# CH32F_V208W-R0.net
KiCad netlist of a schematic drawn in Altium Designer
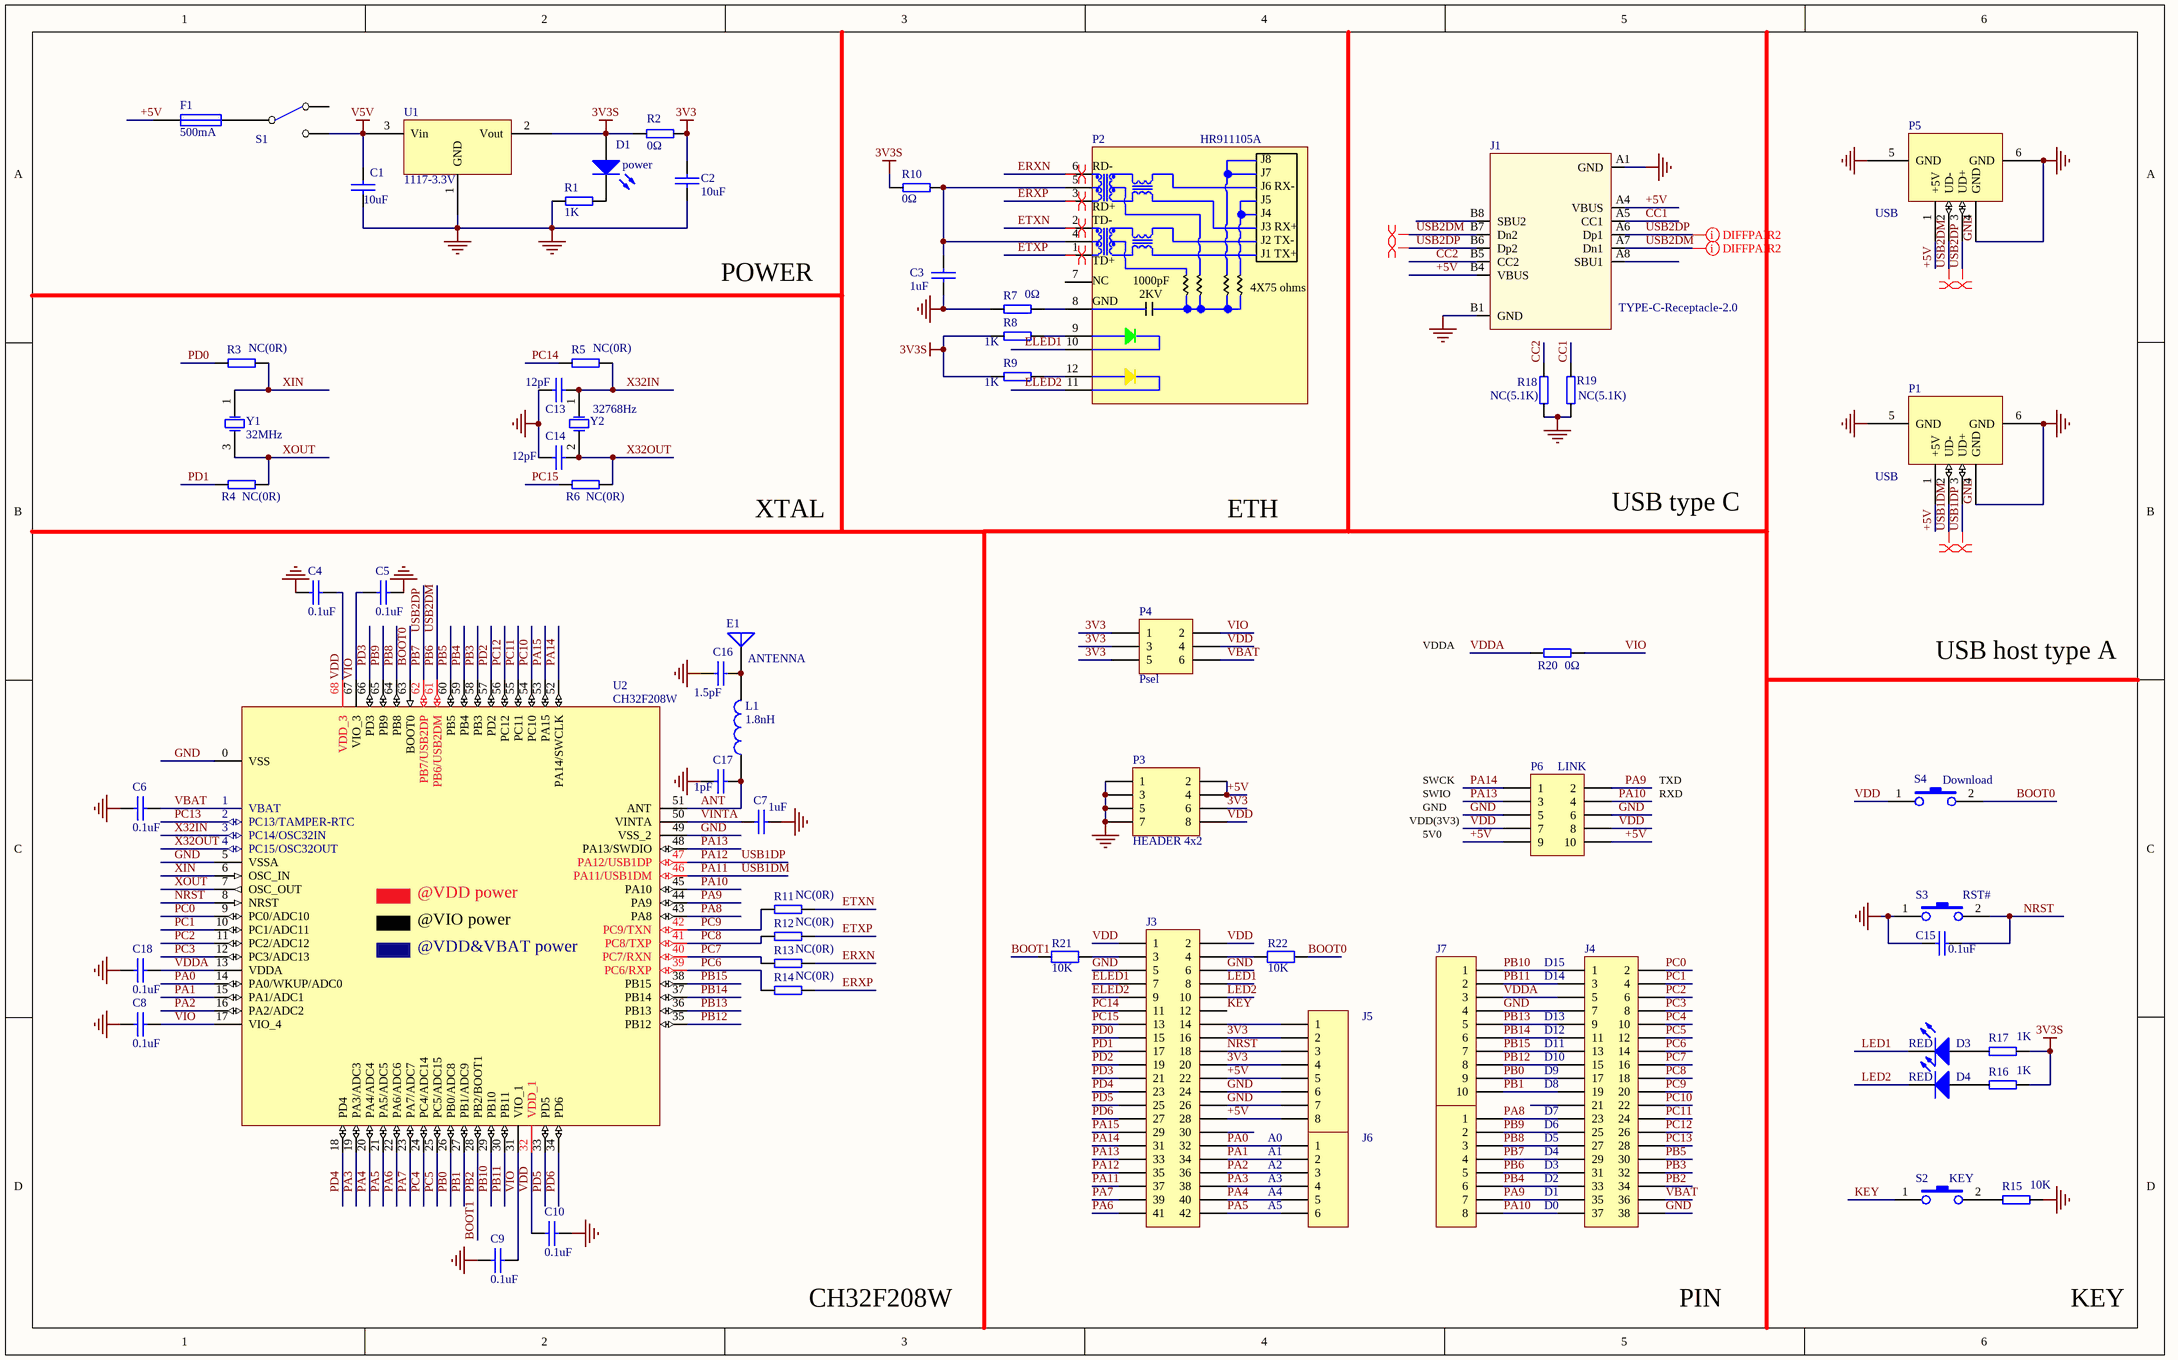
[diagram p0: CH32F&V208W-R0.SchDoc]

(export (version "E")
  (design (tool "Eeschema 10.0.6"))
  (components
    (comp (ref "C1")
      (value "10uF")
      (footprint "3216_C")
      (description "Capacitor")
      (libsource (lib "") (part "CAP_1"))
    )
    (comp (ref "C2")
      (value "10uF")
      (footprint "0603_C")
      (description "Capacitor")
      (libsource (lib "") (part "CAP_1"))
    )
    (comp (ref "C3")
      (value "1uF")
      (footprint "0603_C")
      (description "Capacitor")
      (libsource (lib "") (part "CAP_1"))
    )
    (comp (ref "C4")
      (value "0.1uF")
      (footprint "0603_C")
      (description "Capacitor")
      (libsource (lib "*") (part "CAP"))
    )
    (comp (ref "C5")
      (value "0.1uF")
      (footprint "0603_C")
      (description "Capacitor")
      (libsource (lib "*") (part "CAP"))
    )
    (comp (ref "C6")
      (value "0.1uF")
      (footprint "0603_C")
      (description "Capacitor")
      (libsource (lib "*") (part "CAP"))
    )
    (comp (ref "C7")
      (value "1uF")
      (footprint "0603_C")
      (description "Capacitor")
      (libsource (lib "*") (part "CAP"))
    )
    (comp (ref "C8")
      (value "0.1uF")
      (footprint "0603_C")
      (description "Capacitor")
      (libsource (lib "*") (part "CAP"))
    )
    (comp (ref "C9")
      (value "0.1uF")
      (footprint "0603_C")
      (description "Capacitor")
      (libsource (lib "*") (part "CAP"))
    )
    (comp (ref "C10")
      (value "0.1uF")
      (footprint "0603_C")
      (description "Capacitor")
      (libsource (lib "*") (part "CAP"))
    )
    (comp (ref "C13")
      (value "12pF")
      (footprint "0603_C")
      (description "Capacitor")
      (libsource (lib "") (part "CAP_1"))
    )
    (comp (ref "C14")
      (value "12pF")
      (footprint "0603_C")
      (description "Capacitor")
      (libsource (lib "") (part "CAP_1"))
    )
    (comp (ref "C15")
      (value "0.1uF")
      (footprint "0603_C")
      (description "Capacitor")
      (libsource (lib "*") (part "CAP"))
    )
    (comp (ref "C16")
      (value "1.5pF")
      (footprint "0603_C")
      (description "Capacitor")
      (libsource (lib "*") (part "CAP"))
    )
    (comp (ref "C17")
      (value "1pF")
      (footprint "0603_C")
      (description "Capacitor")
      (libsource (lib "*") (part "CAP"))
    )
    (comp (ref "C18")
      (value "0.1uF")
      (footprint "0603_C")
      (description "Capacitor")
      (libsource (lib "*") (part "CAP"))
    )
    (comp (ref "D1")
      (value "power")
      (footprint "0603+")
      (description "Typical INFRARED GaAs LED")
      (fields (field (name "PUBLISHER") "Altium Limited"))
      (libsource (lib "*") (part "LED0"))
    )
    (comp (ref "D3")
      (value "RED")
      (footprint "0603+")
      (description "Typical INFRARED GaAs LED")
      (fields (field (name "PUBLISHER") "Altium Limited"))
      (libsource (lib "*") (part "LED0"))
    )
    (comp (ref "D4")
      (value "RED")
      (footprint "0603+")
      (description "Typical INFRARED GaAs LED")
      (fields (field (name "PUBLISHER") "Altium Limited"))
      (libsource (lib "*") (part "LED0"))
    )
    (comp (ref "E1")
      (value "ANTENNA")
      (footprint "MYPCB:ANT-F-1-2.4G-1.6")
      (description "Generic Antenna")
      (libsource (lib "*") (part "ANTENNA"))
    )
    (comp (ref "F1")
      (value "500mA")
      (footprint "0603")
      (description "Fuse")
      (libsource (lib "wch_sch_others") (part "FUSE1"))
    )
    (comp (ref "J1")
      (value "TYPE-C-Receptacle-2.0")
      (footprint "TYPE-C-Receptacle-2.0")
      (description "Type-C USB2.0 母座")
      (libsource (lib "Miscellaneous SCH Lib") (part "TYPE-C-Receptacle-2.0"))
    )
    (comp (ref "J3")
      (value "Header 21X2")
      (footprint "IDC42-2.54mm")
      (description "Header, 21-Pin, Dual row")
      (fields (field (name "PUBLISHER") "Altium Limited"))
      (libsource (lib "PCB_Project") (part "Header 21X2"))
    )
    (comp (ref "J4")
      (value "Header 19X2")
      (footprint "IDC38-2.54mm")
      (description "Header, 19-Pin, Dual row")
      (fields (field (name "PUBLISHER") "Altium Limited"))
      (libsource (lib "Miscellaneous Connectors") (part "Header 19X2"))
    )
    (comp (ref "J5")
      (value "Header 8")
      (footprint "SIP8-2.54mm")
      (description "Header, 8-Pin")
      (fields (field (name "PUBLISHER") "Altium Limited"))
      (libsource (lib "Miscellaneous Connectors") (part "Header 8"))
    )
    (comp (ref "J6")
      (value "Header 6")
      (footprint "SIP6-2.54MM")
      (description "Header, 6-Pin")
      (fields (field (name "PUBLISHER") "Altium Limited"))
      (libsource (lib "Miscellaneous Connectors") (part "Header 6"))
    )
    (comp (ref "J7")
      (value "Header 10")
      (footprint "SIP10-2.54mm")
      (description "Header, 10-Pin")
      (fields (field (name "PUBLISHER") "Altium Limited"))
      (libsource (lib "Miscellaneous Connectors") (part "Header 10"))
    )
    (comp (ref "J8")
      (value "Header 8")
      (footprint "SIP8-2.54mm")
      (description "Header, 8-Pin")
      (fields (field (name "PUBLISHER") "Altium Limited"))
      (libsource (lib "") (part "Header 8_1"))
    )
    (comp (ref "L1") (value "1.8nH") (footprint "0603") (libsource (lib "*") (part "INDUCTOR")))
    (comp (ref "P1")
      (value "USB")
      (footprint "USBAF")
      (description "USB Port")
      (libsource (lib "*") (part "USB"))
    )
    (comp (ref "P2") (value "HR911105A") (footprint "HR911105A") (libsource (lib "*") (part "HR911105A")))
    (comp (ref "P3")
      (value "HEADER 4x2")
      (footprint "MYPCB:IDC8-2.54mm")
      (description "Header, 4-Pin, Dual row")
      (libsource (lib "wch_sch_others") (part "HEADER 4x2"))
    )
    (comp (ref "P4")
      (value "Psel")
      (footprint "IDC6-2.54mm")
      (description "Header, 3-Pin, Dual row, Right Angle")
      (fields (field (name "PUBLISHER") "Altium Limited"))
      (libsource (lib "Miscellaneous Connectors") (part "Header 3X2H"))
    )
    (comp (ref "P5")
      (value "USB")
      (footprint "USBAF")
      (description "USB Port")
      (libsource (lib "*") (part "USB"))
    )
    (comp (ref "P6")
      (value "LINK")
      (footprint "IDC10-2.54mm")
      (description "Header, 5-Pin, Dual row, Right Angle")
      (fields (field (name "PUBLISHER") "Altium Limited"))
      (libsource (lib "Miscellaneous Connectors") (part "Header 5X2H"))
    )
    (comp (ref "R1") (value "1K") (footprint "0603") (libsource (lib "wch_sch_others") (part "RES")))
    (comp (ref "R2") (value "0Ω") (footprint "0603") (libsource (lib "wch_sch_others") (part "RES")))
    (comp (ref "R3") (value "NC(0R)") (footprint "0603") (libsource (lib "wch_sch_others") (part "RES")))
    (comp (ref "R4") (value "NC(0R)") (footprint "0603") (libsource (lib "wch_sch_others") (part "RES")))
    (comp (ref "R5") (value "NC(0R)") (footprint "0603") (libsource (lib "wch_sch_others") (part "RES")))
    (comp (ref "R6") (value "NC(0R)") (footprint "0603") (libsource (lib "wch_sch_others") (part "RES")))
    (comp (ref "R7") (value "0Ω") (footprint "0603") (libsource (lib "wch_sch_others") (part "RES")))
    (comp (ref "R8") (value "1K") (footprint "0603") (libsource (lib "wch_sch_others") (part "RES")))
    (comp (ref "R9") (value "1K") (footprint "0603") (libsource (lib "wch_sch_others") (part "RES")))
    (comp (ref "R10") (value "0Ω") (footprint "0603") (libsource (lib "wch_sch_others") (part "RES")))
    (comp (ref "R11") (value "NC(0R)") (footprint "0603") (libsource (lib "wch_sch_others") (part "RES")))
    (comp (ref "R12") (value "NC(0R)") (footprint "0603") (libsource (lib "wch_sch_others") (part "RES")))
    (comp (ref "R13") (value "NC(0R)") (footprint "0603") (libsource (lib "wch_sch_others") (part "RES")))
    (comp (ref "R14") (value "NC(0R)") (footprint "0603") (libsource (lib "wch_sch_others") (part "RES")))
    (comp (ref "R15") (value "10K") (footprint "0603") (libsource (lib "wch_sch_others") (part "RES")))
    (comp (ref "R16") (value "1K") (footprint "0603") (libsource (lib "wch_sch_others") (part "RES")))
    (comp (ref "R17") (value "1K") (footprint "0603") (libsource (lib "wch_sch_others") (part "RES")))
    (comp (ref "R18") (value "NC(5.1K)") (footprint "0603") (libsource (lib "wch_sch_others") (part "RES")))
    (comp (ref "R19") (value "NC(5.1K)") (footprint "0603") (libsource (lib "wch_sch_others") (part "RES")))
    (comp (ref "R20") (value "0Ω") (footprint "0603") (libsource (lib "*") (part "R")))
    (comp (ref "R21")
      (value "10K")
      (footprint "0603")
      (description "Resistor")
      (libsource (lib "Miscellaneous Devices") (part "Res2"))
    )
    (comp (ref "R22")
      (value "10K")
      (footprint "0603")
      (description "Resistor")
      (libsource (lib "Miscellaneous Devices") (part "Res2"))
    )
    (comp (ref "S1") (value "SW SPDT") (footprint "KEY_B") (libsource (lib "*") (part "SW SPDT")))
    (comp (ref "S2")
      (value "KEY")
      (footprint "SMD_6.1x3.65x2.5mm-KEY")
      (libsource (lib "wch_sch_others") (part "KEY1"))
    )
    (comp (ref "S3")
      (value "RST#")
      (footprint "SMD_6.1x3.65x2.5mm-KEY")
      (libsource (lib "wch_sch_others") (part "KEY1"))
    )
    (comp (ref "S4")
      (value "Download")
      (footprint "SMD_6.1x3.65x2.5mm-KEY")
      (libsource (lib "wch_sch_others") (part "KEY1"))
    )
    (comp (ref "U1")
      (value "1117-3.3V")
      (footprint "SOT-223")
      (libsource (lib "wch_sch_others") (part "1117-3.3V"))
    )
    (comp (ref "U2")
      (value "CH32F208W")
      (footprint "QFN68_8x8")
      (description "ARM M3 BLE5.3 MCU, 10M Ethernet, 2*USB, CAN")
      (libsource (lib "CHXXX") (part "CH32F208W"))
    )
    (comp (ref "Y1")
      (value "32MHz")
      (footprint "XT3225")
      (description "Crystal Oscillator")
      (fields (field (name "PUBLISHER") "Altium Limited"))
      (libsource (lib "") (part "XTAL_1"))
    )
    (comp (ref "Y2")
      (value "32768Hz")
      (footprint "FC-135")
      (description "Crystal Oscillator")
      (fields (field (name "PUBLISHER") "Altium Limited"))
      (libsource (lib "*") (part "XTAL"))
    )
  )
  (nets
    (net (code "1") (name "/+5V") (class "Default")
      (node (ref "F1") (pin "1") (pinfunction "1_1") (pintype "passive"))
      (node (ref "J1") (pin "A4") (pinfunction "VBUS_A4") (pintype "passive"))
      (node (ref "J1") (pin "B4") (pinfunction "VBUS_B4") (pintype "passive"))
      (node (ref "J3") (pin "22") (pinfunction "22_22") (pintype "passive"))
      (node (ref "J3") (pin "28") (pinfunction "28_28") (pintype "passive"))
      (node (ref "J5") (pin "5") (pinfunction "5_5") (pintype "passive"))
      (node (ref "J5") (pin "8") (pinfunction "8_8") (pintype "passive"))
      (node (ref "P1") (pin "1") (pinfunction "+5V_1") (pintype "power_in"))
      (node (ref "P3") (pin "2") (pinfunction "2_2") (pintype "passive"))
      (node (ref "P3") (pin "4") (pinfunction "4_4") (pintype "passive"))
      (node (ref "P5") (pin "1") (pinfunction "+5V_1") (pintype "power_in"))
      (node (ref "P6") (pin "10") (pinfunction "10_10") (pintype "passive"))
      (node (ref "P6") (pin "9") (pinfunction "9_9") (pintype "passive"))
    )
    (net (code "2") (name "/ANT") (class "Default")
      (node (ref "C17") (pin "2") (pinfunction "2_2") (pintype "passive"))
      (node (ref "L1") (pin "1") (pinfunction "1_1") (pintype "passive"))
      (node (ref "U2") (pin "51") (pinfunction "ANT_51") (pintype "power_in"))
    )
    (net (code "3") (name "/BOOT0") (class "Default")
      (node (ref "R22") (pin "2") (pinfunction "2_2") (pintype "passive"))
      (node (ref "S4") (pin "2") (pinfunction "2_2") (pintype "passive"))
      (node (ref "U2") (pin "63") (pinfunction "BOOT0_63") (pintype "input"))
    )
    (net (code "4") (name "/BOOT1") (class "Default")
      (node (ref "J4") (pin "34") (pinfunction "34_34") (pintype "passive"))
      (node (ref "R21") (pin "1") (pinfunction "1_1") (pintype "passive"))
      (node (ref "U2") (pin "28") (pinfunction "PB2/BOOT1_28") (pintype "bidirectional"))
    )
    (net (code "5") (name "/CC1") (class "Default")
      (node (ref "J1") (pin "A5") (pinfunction "CC1_A5") (pintype "passive"))
      (node (ref "R19") (pin "1") (pintype "passive"))
    )
    (net (code "6") (name "/CC2") (class "Default")
      (node (ref "J1") (pin "B5") (pinfunction "CC2_B5") (pintype "passive"))
      (node (ref "R18") (pin "1") (pintype "passive"))
    )
    (net (code "7") (name "/ELED1") (class "Default")
      (node (ref "J3") (pin "7") (pinfunction "7_7") (pintype "passive"))
      (node (ref "P2") (pin "10") (pintype "passive"))
    )
    (net (code "8") (name "/ELED2") (class "Default")
      (node (ref "J3") (pin "9") (pinfunction "9_9") (pintype "passive"))
      (node (ref "P2") (pin "11") (pintype "passive"))
    )
    (net (code "9") (name "/ERXN") (class "Default")
      (node (ref "P2") (pin "6") (pintype "passive"))
      (node (ref "R13") (pin "2") (pintype "passive"))
    )
    (net (code "10") (name "/ERXP") (class "Default")
      (node (ref "P2") (pin "3") (pintype "passive"))
      (node (ref "R14") (pin "2") (pintype "passive"))
    )
    (net (code "11") (name "/ETXN") (class "Default")
      (node (ref "P2") (pin "2") (pintype "passive"))
      (node (ref "R11") (pin "2") (pintype "passive"))
    )
    (net (code "12") (name "/ETXP") (class "Default")
      (node (ref "P2") (pin "1") (pintype "passive"))
      (node (ref "R12") (pin "2") (pintype "passive"))
    )
    (net (code "13") (name "/KEY") (class "Default")
      (node (ref "J3") (pin "12") (pinfunction "12_12") (pintype "passive"))
      (node (ref "S2") (pin "1") (pinfunction "1_1") (pintype "passive"))
    )
    (net (code "14") (name "/LED1") (class "Default")
      (node (ref "D3") (pin "2") (pinfunction "K_2") (pintype "passive"))
      (node (ref "J3") (pin "8") (pinfunction "8_8") (pintype "passive"))
    )
    (net (code "15") (name "/LED2") (class "Default")
      (node (ref "D4") (pin "2") (pinfunction "K_2") (pintype "passive"))
      (node (ref "J3") (pin "10") (pinfunction "10_10") (pintype "passive"))
    )
    (net (code "16") (name "/NRST") (class "Default")
      (node (ref "C15") (pin "2") (pinfunction "2_2") (pintype "passive"))
      (node (ref "J3") (pin "18") (pinfunction "18_18") (pintype "passive"))
      (node (ref "J5") (pin "3") (pinfunction "3_3") (pintype "passive"))
      (node (ref "S3") (pin "2") (pinfunction "2_2") (pintype "passive"))
      (node (ref "U2") (pin "8") (pinfunction "NRST_8") (pintype "input"))
    )
    (net (code "17") (name "/PA0") (class "Default")
      (node (ref "J3") (pin "32") (pinfunction "32_32") (pintype "passive"))
      (node (ref "J6") (pin "1") (pinfunction "1_1") (pintype "passive"))
      (node (ref "U2") (pin "14") (pinfunction "PA0/WKUP/ADC0_14") (pintype "bidirectional"))
    )
    (net (code "18") (name "/PA1") (class "Default")
      (node (ref "J3") (pin "34") (pinfunction "34_34") (pintype "passive"))
      (node (ref "J6") (pin "2") (pinfunction "2_2") (pintype "passive"))
      (node (ref "U2") (pin "15") (pinfunction "PA1/ADC1_15") (pintype "bidirectional"))
    )
    (net (code "19") (name "/PA2") (class "Default")
      (node (ref "J3") (pin "36") (pinfunction "36_36") (pintype "passive"))
      (node (ref "J6") (pin "3") (pinfunction "3_3") (pintype "passive"))
      (node (ref "U2") (pin "16") (pinfunction "PA2/ADC2_16") (pintype "bidirectional"))
    )
    (net (code "20") (name "/PA3") (class "Default")
      (node (ref "J3") (pin "38") (pinfunction "38_38") (pintype "passive"))
      (node (ref "J6") (pin "4") (pinfunction "4_4") (pintype "passive"))
      (node (ref "U2") (pin "19") (pinfunction "PA3/ADC3_19") (pintype "bidirectional"))
    )
    (net (code "21") (name "/PA4") (class "Default")
      (node (ref "J3") (pin "40") (pinfunction "40_40") (pintype "passive"))
      (node (ref "J6") (pin "5") (pinfunction "5_5") (pintype "passive"))
      (node (ref "U2") (pin "20") (pinfunction "PA4/ADC4_20") (pintype "bidirectional"))
    )
    (net (code "22") (name "/PA5") (class "Default")
      (node (ref "J3") (pin "42") (pinfunction "42_42") (pintype "passive"))
      (node (ref "J6") (pin "6") (pinfunction "6_6") (pintype "passive"))
      (node (ref "U2") (pin "21") (pinfunction "PA5/ADC5_21") (pintype "bidirectional"))
    )
    (net (code "23") (name "/PA6") (class "Default")
      (node (ref "J3") (pin "41") (pinfunction "41_41") (pintype "passive"))
      (node (ref "U2") (pin "22") (pinfunction "PA6/ADC6_22") (pintype "bidirectional"))
    )
    (net (code "24") (name "/PA7") (class "Default")
      (node (ref "J3") (pin "39") (pinfunction "39_39") (pintype "passive"))
      (node (ref "U2") (pin "23") (pinfunction "PA7/ADC7_23") (pintype "bidirectional"))
    )
    (net (code "25") (name "/PA8") (class "Default")
      (node (ref "J4") (pin "23") (pinfunction "23_23") (pintype "passive"))
      (node (ref "J8") (pin "1") (pinfunction "1_1") (pintype "passive"))
      (node (ref "U2") (pin "43") (pinfunction "PA8_43") (pintype "bidirectional"))
    )
    (net (code "26") (name "/PA9") (class "Default")
      (node (ref "J4") (pin "35") (pinfunction "35_35") (pintype "passive"))
      (node (ref "J8") (pin "7") (pinfunction "7_7") (pintype "passive"))
      (node (ref "P6") (pin "2") (pinfunction "2_2") (pintype "passive"))
      (node (ref "U2") (pin "44") (pinfunction "PA9_44") (pintype "bidirectional"))
    )
    (net (code "27") (name "/PA10") (class "Default")
      (node (ref "J4") (pin "37") (pinfunction "37_37") (pintype "passive"))
      (node (ref "J8") (pin "8") (pinfunction "8_8") (pintype "passive"))
      (node (ref "P6") (pin "4") (pinfunction "4_4") (pintype "passive"))
      (node (ref "U2") (pin "45") (pinfunction "PA10_45") (pintype "bidirectional"))
    )
    (net (code "28") (name "/PA11") (class "Default")
      (node (ref "J3") (pin "37") (pinfunction "37_37") (pintype "passive"))
      (node (ref "P1") (pin "2") (pinfunction "UD-_2") (pintype "bidirectional"))
      (node (ref "U2") (pin "46") (pinfunction "PA11/USB1DM_46") (pintype "bidirectional"))
    )
    (net (code "29") (name "/PA12") (class "Default")
      (node (ref "J3") (pin "35") (pinfunction "35_35") (pintype "passive"))
      (node (ref "P1") (pin "3") (pinfunction "UD+_3") (pintype "bidirectional"))
      (node (ref "U2") (pin "47") (pinfunction "PA12/USB1DP_47") (pintype "bidirectional"))
    )
    (net (code "30") (name "/PA13") (class "Default")
      (node (ref "J3") (pin "33") (pinfunction "33_33") (pintype "passive"))
      (node (ref "P6") (pin "3") (pinfunction "3_3") (pintype "passive"))
      (node (ref "U2") (pin "48") (pinfunction "PA13/SWDIO_48") (pintype "bidirectional"))
    )
    (net (code "31") (name "/PA14") (class "Default")
      (node (ref "J3") (pin "31") (pinfunction "31_31") (pintype "passive"))
      (node (ref "P6") (pin "1") (pinfunction "1_1") (pintype "passive"))
      (node (ref "U2") (pin "52") (pinfunction "PA14/SWCLK_52") (pintype "bidirectional"))
    )
    (net (code "32") (name "/PA15") (class "Default")
      (node (ref "J3") (pin "29") (pinfunction "29_29") (pintype "passive"))
      (node (ref "U2") (pin "53") (pinfunction "PA15_53") (pintype "bidirectional"))
    )
    (net (code "33") (name "/PB0") (class "Default")
      (node (ref "J4") (pin "17") (pinfunction "17_17") (pintype "passive"))
      (node (ref "J7") (pin "9") (pinfunction "9_9") (pintype "passive"))
      (node (ref "U2") (pin "26") (pinfunction "PB0/ADC8_26") (pintype "bidirectional"))
    )
    (net (code "34") (name "/PB1") (class "Default")
      (node (ref "J4") (pin "19") (pinfunction "19_19") (pintype "passive"))
      (node (ref "J7") (pin "10") (pinfunction "10_10") (pintype "passive"))
      (node (ref "U2") (pin "27") (pinfunction "PB1/ADC9_27") (pintype "bidirectional"))
    )
    (net (code "35") (name "/PB3") (class "Default")
      (node (ref "J4") (pin "32") (pinfunction "32_32") (pintype "passive"))
      (node (ref "U2") (pin "58") (pinfunction "PB3_58") (pintype "bidirectional"))
    )
    (net (code "36") (name "/PB4") (class "Default")
      (node (ref "J4") (pin "33") (pinfunction "33_33") (pintype "passive"))
      (node (ref "J8") (pin "6") (pinfunction "6_6") (pintype "passive"))
      (node (ref "U2") (pin "59") (pinfunction "PB4_59") (pintype "bidirectional"))
    )
    (net (code "37") (name "/PB5") (class "Default")
      (node (ref "J4") (pin "30") (pinfunction "30_30") (pintype "passive"))
      (node (ref "U2") (pin "60") (pinfunction "PB5_60") (pintype "bidirectional"))
    )
    (net (code "38") (name "/PB6") (class "Default")
      (node (ref "J1") (pin "A7") (pinfunction "Dn1_A7") (pintype "passive"))
      (node (ref "J1") (pin "B7") (pinfunction "Dn2_B7") (pintype "passive"))
      (node (ref "J4") (pin "31") (pinfunction "31_31") (pintype "passive"))
      (node (ref "J8") (pin "5") (pinfunction "5_5") (pintype "passive"))
      (node (ref "P5") (pin "2") (pinfunction "UD-_2") (pintype "bidirectional"))
      (node (ref "U2") (pin "61") (pinfunction "PB6/USB2DM_61") (pintype "bidirectional"))
    )
    (net (code "39") (name "/PB7") (class "Default")
      (node (ref "J1") (pin "A6") (pinfunction "Dp1_A6") (pintype "passive"))
      (node (ref "J1") (pin "B6") (pinfunction "Dp2_B6") (pintype "passive"))
      (node (ref "J4") (pin "29") (pinfunction "29_29") (pintype "passive"))
      (node (ref "J8") (pin "4") (pinfunction "4_4") (pintype "passive"))
      (node (ref "P5") (pin "3") (pinfunction "UD+_3") (pintype "bidirectional"))
      (node (ref "U2") (pin "62") (pinfunction "PB7/USB2DP_62") (pintype "bidirectional"))
    )
    (net (code "40") (name "/PB8") (class "Default")
      (node (ref "J4") (pin "27") (pinfunction "27_27") (pintype "passive"))
      (node (ref "J8") (pin "3") (pinfunction "3_3") (pintype "passive"))
      (node (ref "U2") (pin "64") (pinfunction "PB8_64") (pintype "bidirectional"))
    )
    (net (code "41") (name "/PB9") (class "Default")
      (node (ref "J4") (pin "25") (pinfunction "25_25") (pintype "passive"))
      (node (ref "J8") (pin "2") (pinfunction "2_2") (pintype "passive"))
      (node (ref "U2") (pin "65") (pinfunction "PB9_65") (pintype "bidirectional"))
    )
    (net (code "42") (name "/PB10") (class "Default")
      (node (ref "J4") (pin "1") (pinfunction "1_1") (pintype "passive"))
      (node (ref "J7") (pin "1") (pinfunction "1_1") (pintype "passive"))
      (node (ref "U2") (pin "29") (pinfunction "PB10_29") (pintype "bidirectional"))
    )
    (net (code "43") (name "/PB11") (class "Default")
      (node (ref "J4") (pin "3") (pinfunction "3_3") (pintype "passive"))
      (node (ref "J7") (pin "2") (pinfunction "2_2") (pintype "passive"))
      (node (ref "U2") (pin "30") (pinfunction "PB11_30") (pintype "bidirectional"))
    )
    (net (code "44") (name "/PB12") (class "Default")
      (node (ref "J4") (pin "15") (pinfunction "15_15") (pintype "passive"))
      (node (ref "J7") (pin "8") (pinfunction "8_8") (pintype "passive"))
      (node (ref "U2") (pin "35") (pinfunction "PB12_35") (pintype "bidirectional"))
    )
    (net (code "45") (name "/PB13") (class "Default")
      (node (ref "J4") (pin "9") (pinfunction "9_9") (pintype "passive"))
      (node (ref "J7") (pin "5") (pinfunction "5_5") (pintype "passive"))
      (node (ref "U2") (pin "36") (pinfunction "PB13_36") (pintype "bidirectional"))
    )
    (net (code "46") (name "/PB14") (class "Default")
      (node (ref "J4") (pin "11") (pinfunction "11_11") (pintype "passive"))
      (node (ref "J7") (pin "6") (pinfunction "6_6") (pintype "passive"))
      (node (ref "U2") (pin "37") (pinfunction "PB14_37") (pintype "bidirectional"))
    )
    (net (code "47") (name "/PB15") (class "Default")
      (node (ref "J4") (pin "13") (pinfunction "13_13") (pintype "passive"))
      (node (ref "J7") (pin "7") (pinfunction "7_7") (pintype "passive"))
      (node (ref "U2") (pin "38") (pinfunction "PB15_38") (pintype "bidirectional"))
    )
    (net (code "48") (name "/PC0") (class "Default")
      (node (ref "J4") (pin "2") (pinfunction "2_2") (pintype "passive"))
      (node (ref "U2") (pin "9") (pinfunction "PC0/ADC10_9") (pintype "bidirectional"))
    )
    (net (code "49") (name "/PC1") (class "Default")
      (node (ref "J4") (pin "4") (pinfunction "4_4") (pintype "passive"))
      (node (ref "U2") (pin "10") (pinfunction "PC1/ADC11_10") (pintype "bidirectional"))
    )
    (net (code "50") (name "/PC2") (class "Default")
      (node (ref "J4") (pin "6") (pinfunction "6_6") (pintype "passive"))
      (node (ref "U2") (pin "11") (pinfunction "PC2/ADC12_11") (pintype "bidirectional"))
    )
    (net (code "51") (name "/PC3") (class "Default")
      (node (ref "J4") (pin "8") (pinfunction "8_8") (pintype "passive"))
      (node (ref "U2") (pin "12") (pinfunction "PC3/ADC13_12") (pintype "bidirectional"))
    )
    (net (code "52") (name "/PC4") (class "Default")
      (node (ref "J4") (pin "10") (pinfunction "10_10") (pintype "passive"))
      (node (ref "U2") (pin "24") (pinfunction "PC4/ADC14_24") (pintype "bidirectional"))
    )
    (net (code "53") (name "/PC5") (class "Default")
      (node (ref "J4") (pin "12") (pinfunction "12_12") (pintype "passive"))
      (node (ref "U2") (pin "25") (pinfunction "PC5/ADC15_25") (pintype "bidirectional"))
    )
    (net (code "54") (name "/PC6") (class "Default")
      (node (ref "J4") (pin "14") (pinfunction "14_14") (pintype "passive"))
      (node (ref "R14") (pin "1") (pintype "passive"))
      (node (ref "U2") (pin "39") (pinfunction "PC6/RXP_39") (pintype "bidirectional"))
    )
    (net (code "55") (name "/PC7") (class "Default")
      (node (ref "J4") (pin "16") (pinfunction "16_16") (pintype "passive"))
      (node (ref "R13") (pin "1") (pintype "passive"))
      (node (ref "U2") (pin "40") (pinfunction "PC7/RXN_40") (pintype "bidirectional"))
    )
    (net (code "56") (name "/PC8") (class "Default")
      (node (ref "J4") (pin "18") (pinfunction "18_18") (pintype "passive"))
      (node (ref "R12") (pin "1") (pintype "passive"))
      (node (ref "U2") (pin "41") (pinfunction "PC8/TXP_41") (pintype "bidirectional"))
    )
    (net (code "57") (name "/PC9") (class "Default")
      (node (ref "J4") (pin "20") (pinfunction "20_20") (pintype "passive"))
      (node (ref "R11") (pin "1") (pintype "passive"))
      (node (ref "U2") (pin "42") (pinfunction "PC9/TXN_42") (pintype "bidirectional"))
    )
    (net (code "58") (name "/PC10") (class "Default")
      (node (ref "J4") (pin "22") (pinfunction "22_22") (pintype "passive"))
      (node (ref "U2") (pin "54") (pinfunction "PC10_54") (pintype "bidirectional"))
    )
    (net (code "59") (name "/PC11") (class "Default")
      (node (ref "J4") (pin "24") (pinfunction "24_24") (pintype "passive"))
      (node (ref "U2") (pin "55") (pinfunction "PC11_55") (pintype "bidirectional"))
    )
    (net (code "60") (name "/PC12") (class "Default")
      (node (ref "J4") (pin "26") (pinfunction "26_26") (pintype "passive"))
      (node (ref "U2") (pin "56") (pinfunction "PC12_56") (pintype "bidirectional"))
    )
    (net (code "61") (name "/PC13") (class "Default")
      (node (ref "J4") (pin "28") (pinfunction "28_28") (pintype "passive"))
      (node (ref "U2") (pin "2") (pinfunction "PC13/TAMPER-RTC_2") (pintype "bidirectional"))
    )
    (net (code "62") (name "/PC14") (class "Default")
      (node (ref "J3") (pin "11") (pinfunction "11_11") (pintype "passive"))
      (node (ref "R5") (pin "1") (pintype "passive"))
    )
    (net (code "63") (name "/PC15") (class "Default")
      (node (ref "J3") (pin "13") (pinfunction "13_13") (pintype "passive"))
      (node (ref "R6") (pin "1") (pintype "passive"))
    )
    (net (code "64") (name "/PD0") (class "Default")
      (node (ref "J3") (pin "15") (pinfunction "15_15") (pintype "passive"))
      (node (ref "R3") (pin "1") (pintype "passive"))
    )
    (net (code "65") (name "/PD1") (class "Default")
      (node (ref "J3") (pin "17") (pinfunction "17_17") (pintype "passive"))
      (node (ref "R4") (pin "1") (pintype "passive"))
    )
    (net (code "66") (name "/PD2") (class "Default")
      (node (ref "J3") (pin "19") (pinfunction "19_19") (pintype "passive"))
      (node (ref "U2") (pin "57") (pinfunction "PD2_57") (pintype "bidirectional"))
    )
    (net (code "67") (name "/PD3") (class "Default")
      (node (ref "J3") (pin "21") (pinfunction "21_21") (pintype "passive"))
      (node (ref "U2") (pin "66") (pinfunction "PD3_66") (pintype "bidirectional"))
    )
    (net (code "68") (name "/PD4") (class "Default")
      (node (ref "J3") (pin "23") (pinfunction "23_23") (pintype "passive"))
      (node (ref "U2") (pin "18") (pinfunction "PD4_18") (pintype "bidirectional"))
    )
    (net (code "69") (name "/PD5") (class "Default")
      (node (ref "J3") (pin "25") (pinfunction "25_25") (pintype "passive"))
      (node (ref "U2") (pin "33") (pinfunction "PD5_33") (pintype "bidirectional"))
    )
    (net (code "70") (name "/PD6") (class "Default")
      (node (ref "J3") (pin "27") (pinfunction "27_27") (pintype "passive"))
      (node (ref "U2") (pin "34") (pinfunction "PD6_34") (pintype "bidirectional"))
    )
    (net (code "71") (name "/VBAT") (class "Default")
      (node (ref "C6") (pin "1") (pinfunction "1_1") (pintype "passive"))
      (node (ref "J4") (pin "36") (pinfunction "36_36") (pintype "passive"))
      (node (ref "P4") (pin "6") (pinfunction "6_6") (pintype "passive"))
      (node (ref "U2") (pin "1") (pinfunction "VBAT_1") (pintype "power_in"))
    )
    (net (code "72") (name "/VDD") (class "Default")
      (node (ref "C10") (pin "2") (pinfunction "2_2") (pintype "passive"))
      (node (ref "C4") (pin "1") (pinfunction "1_1") (pintype "passive"))
      (node (ref "J3") (pin "1") (pinfunction "1_1") (pintype "passive"))
      (node (ref "J3") (pin "2") (pinfunction "2_2") (pintype "passive"))
      (node (ref "P3") (pin "8") (pinfunction "8_8") (pintype "passive"))
      (node (ref "P4") (pin "4") (pinfunction "4_4") (pintype "passive"))
      (node (ref "P6") (pin "7") (pinfunction "7_7") (pintype "passive"))
      (node (ref "P6") (pin "8") (pinfunction "8_8") (pintype "passive"))
      (node (ref "S4") (pin "1") (pinfunction "1_1") (pintype "passive"))
      (node (ref "U2") (pin "32") (pinfunction "VDD_1_32") (pintype "power_in"))
      (node (ref "U2") (pin "68") (pinfunction "VDD_3_68") (pintype "power_in"))
    )
    (net (code "73") (name "/VDDA") (class "Default")
      (node (ref "C18") (pin "1") (pinfunction "1_1") (pintype "passive"))
      (node (ref "J4") (pin "5") (pinfunction "5_5") (pintype "passive"))
      (node (ref "J7") (pin "3") (pinfunction "3_3") (pintype "passive"))
      (node (ref "R20") (pin "2") (pinfunction "2_2") (pintype "passive"))
      (node (ref "U2") (pin "13") (pinfunction "VDDA_13") (pintype "power_in"))
    )
    (net (code "74") (name "/VINTA") (class "Default")
      (node (ref "C7") (pin "1") (pinfunction "1_1") (pintype "passive"))
      (node (ref "U2") (pin "50") (pinfunction "VINTA_50") (pintype "power_in"))
    )
    (net (code "75") (name "/VIO") (class "Default")
      (node (ref "C5") (pin "2") (pinfunction "2_2") (pintype "passive"))
      (node (ref "C8") (pin "1") (pinfunction "1_1") (pintype "passive"))
      (node (ref "C9") (pin "1") (pinfunction "1_1") (pintype "passive"))
      (node (ref "P4") (pin "2") (pinfunction "2_2") (pintype "passive"))
      (node (ref "R20") (pin "1") (pinfunction "1_1") (pintype "passive"))
      (node (ref "U2") (pin "17") (pinfunction "VIO_4_17") (pintype "power_in"))
      (node (ref "U2") (pin "31") (pinfunction "VIO_1_31") (pintype "power_in"))
      (node (ref "U2") (pin "67") (pinfunction "VIO_3_67") (pintype "power_in"))
    )
    (net (code "76") (name "/X32IN") (class "Default")
      (node (ref "C13") (pin "2") (pinfunction "2_2") (pintype "passive"))
      (node (ref "R5") (pin "2") (pintype "passive"))
      (node (ref "U2") (pin "3") (pinfunction "PC14/OSC32IN_3") (pintype "bidirectional"))
      (node (ref "Y2") (pin "1") (pinfunction "OSC1_1") (pintype "passive"))
    )
    (net (code "77") (name "/X32OUT") (class "Default")
      (node (ref "C14") (pin "2") (pinfunction "2_2") (pintype "passive"))
      (node (ref "R6") (pin "2") (pintype "passive"))
      (node (ref "U2") (pin "4") (pinfunction "PC15/OSC32OUT_4") (pintype "bidirectional"))
      (node (ref "Y2") (pin "2") (pinfunction "OSC2_2") (pintype "passive"))
    )
    (net (code "78") (name "/XIN") (class "Default")
      (node (ref "R3") (pin "2") (pintype "passive"))
      (node (ref "U2") (pin "6") (pinfunction "OSC_IN_6") (pintype "input"))
      (node (ref "Y1") (pin "1") (pinfunction "OSC1_1") (pintype "passive"))
    )
    (net (code "79") (name "/XOUT") (class "Default")
      (node (ref "R4") (pin "2") (pintype "passive"))
      (node (ref "U2") (pin "7") (pinfunction "OSC_OUT_7") (pintype "output"))
      (node (ref "Y1") (pin "3") (pinfunction "OSC2_3") (pintype "passive"))
    )
    (net (code "80") (name "3V3") (class "Default")
      (node (ref "C2") (pin "1") (pinfunction "1_1") (pintype "passive"))
      (node (ref "J3") (pin "16") (pinfunction "16_16") (pintype "passive"))
      (node (ref "J3") (pin "20") (pinfunction "20_20") (pintype "passive"))
      (node (ref "J5") (pin "2") (pinfunction "2_2") (pintype "passive"))
      (node (ref "J5") (pin "4") (pinfunction "4_4") (pintype "passive"))
      (node (ref "P3") (pin "6") (pinfunction "6_6") (pintype "passive"))
      (node (ref "P4") (pin "1") (pinfunction "1_1") (pintype "passive"))
      (node (ref "P4") (pin "3") (pinfunction "3_3") (pintype "passive"))
      (node (ref "P4") (pin "5") (pinfunction "5_5") (pintype "passive"))
      (node (ref "R2") (pin "1") (pintype "passive"))
    )
    (net (code "81") (name "3V3S") (class "Default")
      (node (ref "D1") (pin "1") (pinfunction "A_1") (pintype "passive"))
      (node (ref "R10") (pin "2") (pintype "passive"))
      (node (ref "R16") (pin "1") (pintype "passive"))
      (node (ref "R17") (pin "1") (pintype "passive"))
      (node (ref "R2") (pin "2") (pintype "passive"))
      (node (ref "R8") (pin "1") (pintype "passive"))
      (node (ref "R9") (pin "1") (pintype "passive"))
      (node (ref "U1") (pin "2") (pinfunction "Vout_2") (pintype "passive"))
    )
    (net (code "82") (name "GND") (class "Default")
      (node (ref "C1") (pin "2") (pinfunction "2_2") (pintype "passive"))
      (node (ref "C10") (pin "1") (pinfunction "1_1") (pintype "passive"))
      (node (ref "C13") (pin "1") (pinfunction "1_1") (pintype "passive"))
      (node (ref "C14") (pin "1") (pinfunction "1_1") (pintype "passive"))
      (node (ref "C15") (pin "1") (pinfunction "1_1") (pintype "passive"))
      (node (ref "C16") (pin "1") (pinfunction "1_1") (pintype "passive"))
      (node (ref "C17") (pin "1") (pinfunction "1_1") (pintype "passive"))
      (node (ref "C18") (pin "2") (pinfunction "2_2") (pintype "passive"))
      (node (ref "C2") (pin "2") (pinfunction "2_2") (pintype "passive"))
      (node (ref "C3") (pin "1") (pinfunction "1_1") (pintype "passive"))
      (node (ref "C4") (pin "2") (pinfunction "2_2") (pintype "passive"))
      (node (ref "C5") (pin "1") (pinfunction "1_1") (pintype "passive"))
      (node (ref "C6") (pin "2") (pinfunction "2_2") (pintype "passive"))
      (node (ref "C7") (pin "2") (pinfunction "2_2") (pintype "passive"))
      (node (ref "C8") (pin "2") (pinfunction "2_2") (pintype "passive"))
      (node (ref "C9") (pin "2") (pinfunction "2_2") (pintype "passive"))
      (node (ref "J1") (pin "A1") (pinfunction "GND_A1") (pintype "passive"))
      (node (ref "J1") (pin "B1") (pinfunction "GND_B1") (pintype "passive"))
      (node (ref "J3") (pin "24") (pinfunction "24_24") (pintype "passive"))
      (node (ref "J3") (pin "26") (pinfunction "26_26") (pintype "passive"))
      (node (ref "J3") (pin "5") (pinfunction "5_5") (pintype "passive"))
      (node (ref "J3") (pin "6") (pinfunction "6_6") (pintype "passive"))
      (node (ref "J4") (pin "38") (pinfunction "38_38") (pintype "passive"))
      (node (ref "J4") (pin "7") (pinfunction "7_7") (pintype "passive"))
      (node (ref "J5") (pin "6") (pinfunction "6_6") (pintype "passive"))
      (node (ref "J5") (pin "7") (pinfunction "7_7") (pintype "passive"))
      (node (ref "J7") (pin "4") (pinfunction "4_4") (pintype "passive"))
      (node (ref "P1") (pin "4") (pinfunction "GND_4") (pintype "power_in"))
      (node (ref "P1") (pin "5") (pinfunction "GND_5") (pintype "power_in"))
      (node (ref "P1") (pin "6") (pinfunction "GND_6") (pintype "power_in"))
      (node (ref "P3") (pin "1") (pinfunction "1_1") (pintype "passive"))
      (node (ref "P3") (pin "3") (pinfunction "3_3") (pintype "passive"))
      (node (ref "P3") (pin "5") (pinfunction "5_5") (pintype "passive"))
      (node (ref "P3") (pin "7") (pinfunction "7_7") (pintype "passive"))
      (node (ref "P5") (pin "4") (pinfunction "GND_4") (pintype "power_in"))
      (node (ref "P5") (pin "5") (pinfunction "GND_5") (pintype "power_in"))
      (node (ref "P5") (pin "6") (pinfunction "GND_6") (pintype "power_in"))
      (node (ref "P6") (pin "5") (pinfunction "5_5") (pintype "passive"))
      (node (ref "P6") (pin "6") (pinfunction "6_6") (pintype "passive"))
      (node (ref "R1") (pin "1") (pintype "passive"))
      (node (ref "R15") (pin "1") (pintype "passive"))
      (node (ref "R18") (pin "2") (pintype "passive"))
      (node (ref "R19") (pin "2") (pintype "passive"))
      (node (ref "R7") (pin "1") (pintype "passive"))
      (node (ref "S3") (pin "1") (pinfunction "1_1") (pintype "passive"))
      (node (ref "U1") (pin "1") (pinfunction "GND_1") (pintype "passive"))
      (node (ref "U2") (pin "0") (pinfunction "VSS_0") (pintype "power_in"))
      (node (ref "U2") (pin "49") (pinfunction "VSS_2_49") (pintype "power_in"))
      (node (ref "U2") (pin "5") (pinfunction "VSSA_5") (pintype "power_in"))
    )
    (net (code "83") (name "Net-(C3-Pad2)") (class "Default")
      (node (ref "C3") (pin "2") (pinfunction "2_2") (pintype "passive"))
      (node (ref "P2") (pin "4") (pintype "passive"))
      (node (ref "P2") (pin "5") (pintype "passive"))
      (node (ref "R10") (pin "1") (pintype "passive"))
    )
    (net (code "84") (name "Net-(D1-K)") (class "Default")
      (node (ref "D1") (pin "2") (pinfunction "K_2") (pintype "passive"))
      (node (ref "R1") (pin "2") (pintype "passive"))
    )
    (net (code "85") (name "Net-(D3-A)") (class "Default")
      (node (ref "D3") (pin "1") (pinfunction "A_1") (pintype "passive"))
      (node (ref "R17") (pin "2") (pintype "passive"))
    )
    (net (code "86") (name "Net-(D4-A)") (class "Default")
      (node (ref "D4") (pin "1") (pinfunction "A_1") (pintype "passive"))
      (node (ref "R16") (pin "2") (pintype "passive"))
    )
    (net (code "87") (name "Net-(E1-A)") (class "Default")
      (node (ref "C16") (pin "2") (pinfunction "2_2") (pintype "passive"))
      (node (ref "E1") (pin "1") (pinfunction "A_1") (pintype "passive"))
      (node (ref "L1") (pin "2") (pinfunction "2_2") (pintype "passive"))
    )
    (net (code "88") (name "Net-(J3-Pad3)") (class "Default")
      (node (ref "J3") (pin "3") (pinfunction "3_3") (pintype "passive"))
      (node (ref "R21") (pin "2") (pinfunction "2_2") (pintype "passive"))
    )
    (net (code "89") (name "Net-(J3-Pad4)") (class "Default")
      (node (ref "J3") (pin "4") (pinfunction "4_4") (pintype "passive"))
      (node (ref "R22") (pin "1") (pinfunction "1_1") (pintype "passive"))
    )
    (net (code "90") (name "Net-(J3-Pad14)") (class "Default")
      (node (ref "J3") (pin "14") (pinfunction "14_14") (pintype "passive"))
      (node (ref "J5") (pin "1") (pinfunction "1_1") (pintype "passive"))
    )
    (net (code "91") (name "Net-(P2-Pad8)") (class "Default")
      (node (ref "P2") (pin "8") (pintype "passive"))
      (node (ref "R7") (pin "2") (pintype "passive"))
    )
    (net (code "92") (name "Net-(P2-Pad9)") (class "Default")
      (node (ref "P2") (pin "9") (pintype "passive"))
      (node (ref "R8") (pin "2") (pintype "passive"))
    )
    (net (code "93") (name "Net-(P2-Pad12)") (class "Default")
      (node (ref "P2") (pin "12") (pintype "passive"))
      (node (ref "R9") (pin "2") (pintype "passive"))
    )
    (net (code "94") (name "Net-(R15-Pad2)") (class "Default")
      (node (ref "R15") (pin "2") (pintype "passive"))
      (node (ref "S2") (pin "2") (pinfunction "2_2") (pintype "passive"))
    )
    (net (code "95") (name "Net-(S1-COMMON)") (class "Default")
      (node (ref "F1") (pin "2") (pinfunction "2_2") (pintype "passive"))
      (node (ref "S1") (pin "1") (pinfunction "COMMON_1") (pintype "passive"))
    )
    (net (code "96") (name "V5V") (class "Default")
      (node (ref "C1") (pin "1") (pinfunction "1_1") (pintype "passive"))
      (node (ref "S1") (pin "2") (pinfunction "NC_2") (pintype "passive"))
      (node (ref "U1") (pin "3") (pinfunction "Vin_3") (pintype "passive"))
    )
    (net (code "97") (name "unconnected-(J1-SBU1-PadA8)") (class "Default")
      (node (ref "J1") (pin "A8") (pinfunction "SBU1_A8") (pintype "passive"))
    )
    (net (code "98") (name "unconnected-(J1-SBU2-PadB8)") (class "Default")
      (node (ref "J1") (pin "B8") (pinfunction "SBU2_B8") (pintype "passive"))
    )
    (net (code "99") (name "unconnected-(J3-Pad30)") (class "Default")
      (node (ref "J3") (pin "30") (pinfunction "30_30") (pintype "passive"))
    )
    (net (code "100") (name "unconnected-(J4-Pad21)") (class "Default")
      (node (ref "J4") (pin "21") (pinfunction "21_21") (pintype "passive"))
    )
    (net (code "101") (name "unconnected-(P2-Pad7)") (class "Default")
      (node (ref "P2") (pin "7") (pintype "passive"))
    )
    (net (code "102") (name "unconnected-(S1-NO-Pad3)") (class "Default")
      (node (ref "S1") (pin "3") (pinfunction "NO_3") (pintype "passive"))
    )
  )
)
